# QS30-Main.net
KiCad netlist of a schematic drawn in Altium Designer
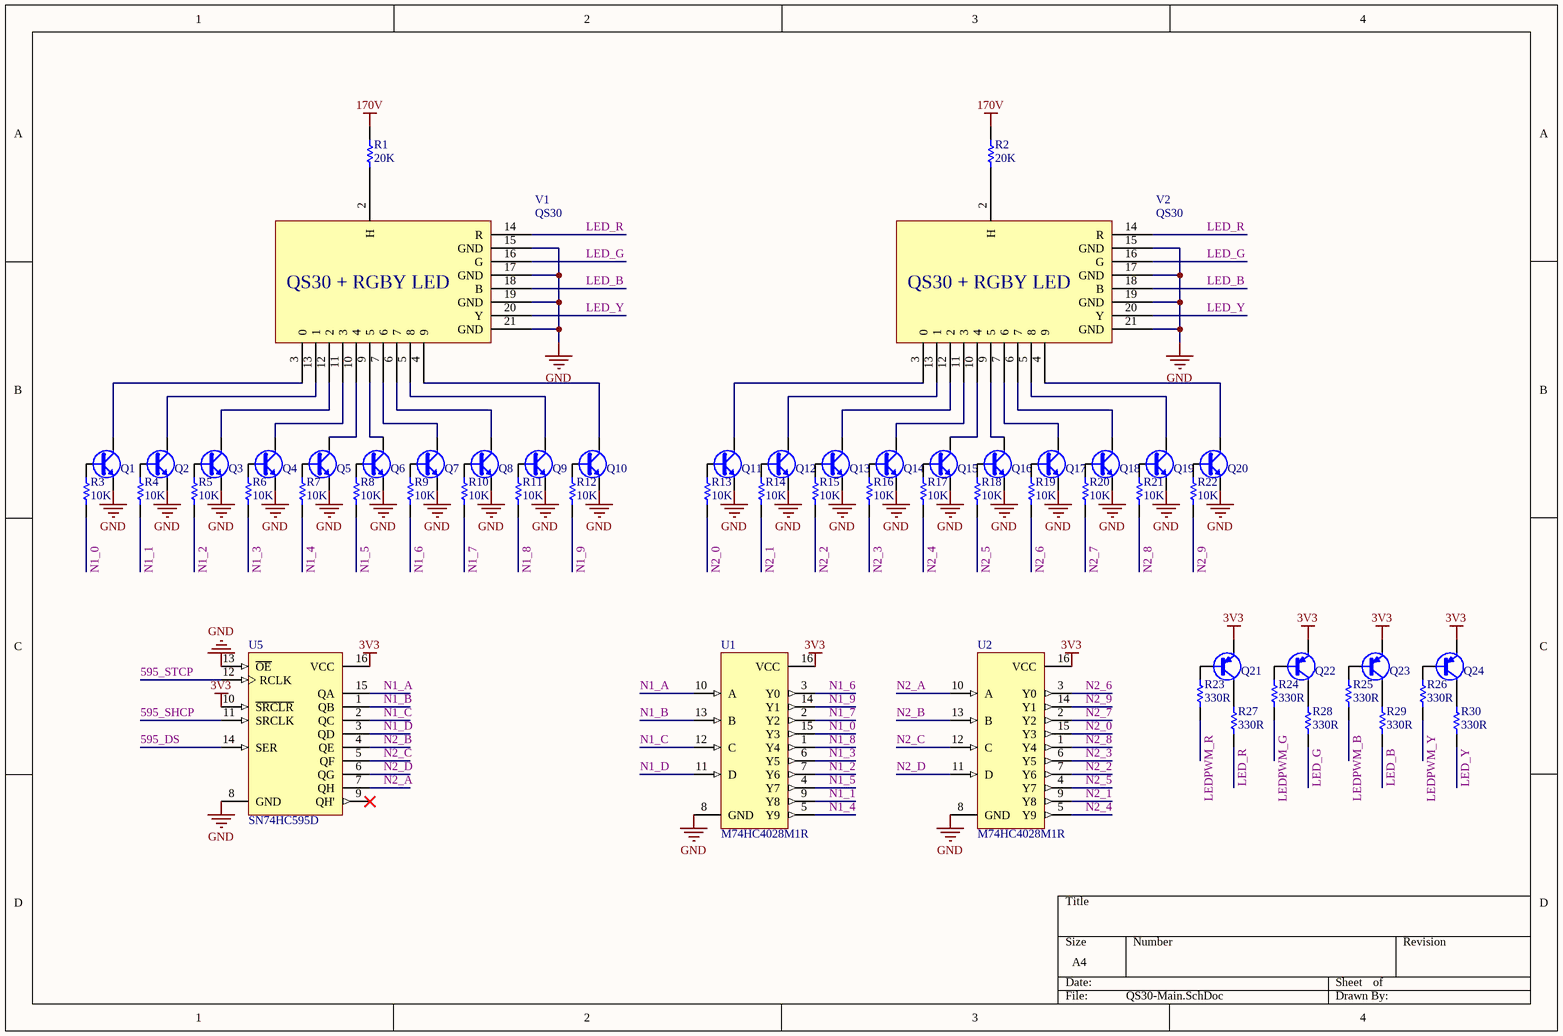
[diagram p0: QS30-Main.SchDoc]

(export (version "E")
  (design (tool "Eeschema 10.0.6"))
  (components
    (comp (ref "Q1") (value "MMBTA42") (footprint "SOT-23B_L") (libsource (lib "MINE") (part "MMBTA42")))
    (comp (ref "Q2") (value "MMBTA42") (footprint "SOT-23B_L") (libsource (lib "MINE") (part "MMBTA42")))
    (comp (ref "Q3") (value "MMBTA42") (footprint "SOT-23B_L") (libsource (lib "MINE") (part "MMBTA42")))
    (comp (ref "Q4") (value "MMBTA42") (footprint "SOT-23B_L") (libsource (lib "MINE") (part "MMBTA42")))
    (comp (ref "Q5") (value "MMBTA42") (footprint "SOT-23B_L") (libsource (lib "MINE") (part "MMBTA42")))
    (comp (ref "Q6") (value "MMBTA42") (footprint "SOT-23B_L") (libsource (lib "MINE") (part "MMBTA42")))
    (comp (ref "Q7") (value "MMBTA42") (footprint "SOT-23B_L") (libsource (lib "MINE") (part "MMBTA42")))
    (comp (ref "Q8") (value "MMBTA42") (footprint "SOT-23B_L") (libsource (lib "MINE") (part "MMBTA42")))
    (comp (ref "Q9") (value "MMBTA42") (footprint "SOT-23B_L") (libsource (lib "MINE") (part "MMBTA42")))
    (comp (ref "Q10") (value "MMBTA42") (footprint "SOT-23B_L") (libsource (lib "MINE") (part "MMBTA42")))
    (comp (ref "Q11") (value "MMBTA42") (footprint "SOT-23B_L") (libsource (lib "MINE") (part "MMBTA42")))
    (comp (ref "Q12") (value "MMBTA42") (footprint "SOT-23B_L") (libsource (lib "MINE") (part "MMBTA42")))
    (comp (ref "Q13") (value "MMBTA42") (footprint "SOT-23B_L") (libsource (lib "MINE") (part "MMBTA42")))
    (comp (ref "Q14") (value "MMBTA42") (footprint "SOT-23B_L") (libsource (lib "MINE") (part "MMBTA42")))
    (comp (ref "Q15") (value "MMBTA42") (footprint "SOT-23B_L") (libsource (lib "MINE") (part "MMBTA42")))
    (comp (ref "Q16") (value "MMBTA42") (footprint "SOT-23B_L") (libsource (lib "MINE") (part "MMBTA42")))
    (comp (ref "Q17") (value "MMBTA42") (footprint "SOT-23B_L") (libsource (lib "MINE") (part "MMBTA42")))
    (comp (ref "Q18") (value "MMBTA42") (footprint "SOT-23B_L") (libsource (lib "MINE") (part "MMBTA42")))
    (comp (ref "Q19") (value "MMBTA42") (footprint "SOT-23B_L") (libsource (lib "MINE") (part "MMBTA42")))
    (comp (ref "Q20") (value "MMBTA42") (footprint "SOT-23B_L") (libsource (lib "MINE") (part "MMBTA42")))
    (comp (ref "Q21")
      (value "9012 8550")
      (footprint "SOT-23")
      (description "PNP")
      (libsource (lib "常用封装库") (part "9012 8550"))
    )
    (comp (ref "Q22")
      (value "9012 8550")
      (footprint "SOT-23")
      (description "PNP")
      (libsource (lib "常用封装库") (part "9012 8550"))
    )
    (comp (ref "Q23")
      (value "9012 8550")
      (footprint "SOT-23")
      (description "PNP")
      (libsource (lib "常用封装库") (part "9012 8550"))
    )
    (comp (ref "Q24")
      (value "9012 8550")
      (footprint "SOT-23")
      (description "PNP")
      (libsource (lib "常用封装库") (part "9012 8550"))
    )
    (comp (ref "R1")
      (value "20K")
      (footprint "6-0805_N")
      (description "Resistor")
      (fields (field (name "Comment") "Res1") (field (name "PUBLISHER") "Altium Limited"))
      (libsource (lib "Miscellaneous Devices") (part "Res1"))
    )
    (comp (ref "R2")
      (value "20K")
      (footprint "6-0805_N")
      (description "Resistor")
      (fields (field (name "Comment") "Res1") (field (name "PUBLISHER") "Altium Limited"))
      (libsource (lib "Miscellaneous Devices") (part "Res1"))
    )
    (comp (ref "R3")
      (value "10K")
      (footprint "6-0805_N")
      (description "Resistor")
      (fields (field (name "Comment") "Res1") (field (name "PUBLISHER") "Altium Limited"))
      (libsource (lib "Miscellaneous Devices") (part "Res1"))
    )
    (comp (ref "R4")
      (value "10K")
      (footprint "6-0805_N")
      (description "Resistor")
      (fields (field (name "Comment") "Res1") (field (name "PUBLISHER") "Altium Limited"))
      (libsource (lib "Miscellaneous Devices") (part "Res1"))
    )
    (comp (ref "R5")
      (value "10K")
      (footprint "6-0805_N")
      (description "Resistor")
      (fields (field (name "Comment") "Res1") (field (name "PUBLISHER") "Altium Limited"))
      (libsource (lib "Miscellaneous Devices") (part "Res1"))
    )
    (comp (ref "R6")
      (value "10K")
      (footprint "6-0805_N")
      (description "Resistor")
      (fields (field (name "Comment") "Res1") (field (name "PUBLISHER") "Altium Limited"))
      (libsource (lib "Miscellaneous Devices") (part "Res1"))
    )
    (comp (ref "R7")
      (value "10K")
      (footprint "6-0805_N")
      (description "Resistor")
      (fields (field (name "Comment") "Res1") (field (name "PUBLISHER") "Altium Limited"))
      (libsource (lib "Miscellaneous Devices") (part "Res1"))
    )
    (comp (ref "R8")
      (value "10K")
      (footprint "6-0805_N")
      (description "Resistor")
      (fields (field (name "Comment") "Res1") (field (name "PUBLISHER") "Altium Limited"))
      (libsource (lib "Miscellaneous Devices") (part "Res1"))
    )
    (comp (ref "R9")
      (value "10K")
      (footprint "6-0805_N")
      (description "Resistor")
      (fields (field (name "Comment") "Res1") (field (name "PUBLISHER") "Altium Limited"))
      (libsource (lib "Miscellaneous Devices") (part "Res1"))
    )
    (comp (ref "R10")
      (value "10K")
      (footprint "6-0805_N")
      (description "Resistor")
      (fields (field (name "Comment") "Res1") (field (name "PUBLISHER") "Altium Limited"))
      (libsource (lib "Miscellaneous Devices") (part "Res1"))
    )
    (comp (ref "R11")
      (value "10K")
      (footprint "6-0805_N")
      (description "Resistor")
      (fields (field (name "Comment") "Res1") (field (name "PUBLISHER") "Altium Limited"))
      (libsource (lib "Miscellaneous Devices") (part "Res1"))
    )
    (comp (ref "R12")
      (value "10K")
      (footprint "6-0805_N")
      (description "Resistor")
      (fields (field (name "Comment") "Res1") (field (name "PUBLISHER") "Altium Limited"))
      (libsource (lib "Miscellaneous Devices") (part "Res1"))
    )
    (comp (ref "R13")
      (value "10K")
      (footprint "6-0805_N")
      (description "Resistor")
      (fields (field (name "Comment") "Res1") (field (name "PUBLISHER") "Altium Limited"))
      (libsource (lib "Miscellaneous Devices") (part "Res1"))
    )
    (comp (ref "R14")
      (value "10K")
      (footprint "6-0805_N")
      (description "Resistor")
      (fields (field (name "Comment") "Res1") (field (name "PUBLISHER") "Altium Limited"))
      (libsource (lib "Miscellaneous Devices") (part "Res1"))
    )
    (comp (ref "R15")
      (value "10K")
      (footprint "6-0805_N")
      (description "Resistor")
      (fields (field (name "Comment") "Res1") (field (name "PUBLISHER") "Altium Limited"))
      (libsource (lib "Miscellaneous Devices") (part "Res1"))
    )
    (comp (ref "R16")
      (value "10K")
      (footprint "6-0805_N")
      (description "Resistor")
      (fields (field (name "Comment") "Res1") (field (name "PUBLISHER") "Altium Limited"))
      (libsource (lib "Miscellaneous Devices") (part "Res1"))
    )
    (comp (ref "R17")
      (value "10K")
      (footprint "6-0805_N")
      (description "Resistor")
      (fields (field (name "Comment") "Res1") (field (name "PUBLISHER") "Altium Limited"))
      (libsource (lib "Miscellaneous Devices") (part "Res1"))
    )
    (comp (ref "R18")
      (value "10K")
      (footprint "6-0805_N")
      (description "Resistor")
      (fields (field (name "Comment") "Res1") (field (name "PUBLISHER") "Altium Limited"))
      (libsource (lib "Miscellaneous Devices") (part "Res1"))
    )
    (comp (ref "R19")
      (value "10K")
      (footprint "6-0805_N")
      (description "Resistor")
      (fields (field (name "Comment") "Res1") (field (name "PUBLISHER") "Altium Limited"))
      (libsource (lib "Miscellaneous Devices") (part "Res1"))
    )
    (comp (ref "R20")
      (value "10K")
      (footprint "6-0805_N")
      (description "Resistor")
      (fields (field (name "Comment") "Res1") (field (name "PUBLISHER") "Altium Limited"))
      (libsource (lib "Miscellaneous Devices") (part "Res1"))
    )
    (comp (ref "R21")
      (value "10K")
      (footprint "6-0805_N")
      (description "Resistor")
      (fields (field (name "Comment") "Res1") (field (name "PUBLISHER") "Altium Limited"))
      (libsource (lib "Miscellaneous Devices") (part "Res1"))
    )
    (comp (ref "R22")
      (value "10K")
      (footprint "6-0805_N")
      (description "Resistor")
      (fields (field (name "Comment") "Res1") (field (name "PUBLISHER") "Altium Limited"))
      (libsource (lib "Miscellaneous Devices") (part "Res1"))
    )
    (comp (ref "R23")
      (value "330R")
      (footprint "6-0805_N")
      (description "Resistor")
      (fields (field (name "Comment") "Res1") (field (name "PUBLISHER") "Altium Limited"))
      (libsource (lib "Miscellaneous Devices") (part "Res1"))
    )
    (comp (ref "R24")
      (value "330R")
      (footprint "6-0805_N")
      (description "Resistor")
      (fields (field (name "Comment") "Res1") (field (name "PUBLISHER") "Altium Limited"))
      (libsource (lib "Miscellaneous Devices") (part "Res1"))
    )
    (comp (ref "R25")
      (value "330R")
      (footprint "6-0805_N")
      (description "Resistor")
      (fields (field (name "Comment") "Res1") (field (name "PUBLISHER") "Altium Limited"))
      (libsource (lib "Miscellaneous Devices") (part "Res1"))
    )
    (comp (ref "R26")
      (value "330R")
      (footprint "6-0805_N")
      (description "Resistor")
      (fields (field (name "Comment") "Res1") (field (name "PUBLISHER") "Altium Limited"))
      (libsource (lib "Miscellaneous Devices") (part "Res1"))
    )
    (comp (ref "R27")
      (value "330R")
      (footprint "6-0805_N")
      (description "Resistor")
      (fields (field (name "Comment") "Res1") (field (name "PUBLISHER") "Altium Limited"))
      (libsource (lib "Miscellaneous Devices") (part "Res1"))
    )
    (comp (ref "R28")
      (value "330R")
      (footprint "6-0805_N")
      (description "Resistor")
      (fields (field (name "Comment") "Res1") (field (name "PUBLISHER") "Altium Limited"))
      (libsource (lib "Miscellaneous Devices") (part "Res1"))
    )
    (comp (ref "R29")
      (value "330R")
      (footprint "6-0805_N")
      (description "Resistor")
      (fields (field (name "Comment") "Res1") (field (name "PUBLISHER") "Altium Limited"))
      (libsource (lib "Miscellaneous Devices") (part "Res1"))
    )
    (comp (ref "R30")
      (value "330R")
      (footprint "6-0805_N")
      (description "Resistor")
      (fields (field (name "Comment") "Res1") (field (name "PUBLISHER") "Altium Limited"))
      (libsource (lib "Miscellaneous Devices") (part "Res1"))
    )
    (comp (ref "U1")
      (value "M74HC4028M1R")
      (footprint "SO16_N")
      (description "BCD-to-Decimal Decoder")
      (fields (field (name "PUBLISHER") "Altium Limited"))
      (libsource (lib "ST Logic Decoder") (part "M74HC4028M1R"))
    )
    (comp (ref "U2")
      (value "M74HC4028M1R")
      (footprint "SO16_N")
      (description "BCD-to-Decimal Decoder")
      (fields (field (name "PUBLISHER") "Altium Limited"))
      (libsource (lib "ST Logic Decoder") (part "M74HC4028M1R"))
    )
    (comp (ref "U5")
      (value "SN74HC595D")
      (footprint "D016_N")
      (description "8-Bit Shift Register with 3-State Output Registers")
      (fields (field (name "PUBLISHER") "Altium Limited"))
      (libsource (lib "TI Logic Register") (part "SN74HC595D"))
    )
    (comp (ref "V1") (value "QS30") (footprint "QS30") (libsource (lib "常用封装库") (part "QS30")))
    (comp (ref "V2") (value "QS30") (footprint "QS30") (libsource (lib "常用封装库") (part "QS30")))
  )
  (nets
    (net (code "1") (name "/595_DS") (class "Default")
      (node (ref "U5") (pin "14") (pinfunction "SER_14") (pintype "input"))
    )
    (net (code "2") (name "/595_SHCP") (class "Default")
      (node (ref "U5") (pin "11") (pinfunction "SRCLK_11") (pintype "input"))
    )
    (net (code "3") (name "/595_STCP") (class "Default")
      (node (ref "U5") (pin "12") (pinfunction "RCLK_12") (pintype "input"))
    )
    (net (code "4") (name "/LEDPWM_B") (class "Default")
      (node (ref "R25") (pin "1") (pinfunction "1_1") (pintype "passive"))
    )
    (net (code "5") (name "/LEDPWM_G") (class "Default")
      (node (ref "R24") (pin "1") (pinfunction "1_1") (pintype "passive"))
    )
    (net (code "6") (name "/LEDPWM_R") (class "Default")
      (node (ref "R23") (pin "1") (pinfunction "1_1") (pintype "passive"))
    )
    (net (code "7") (name "/LEDPWM_Y") (class "Default")
      (node (ref "R26") (pin "1") (pinfunction "1_1") (pintype "passive"))
    )
    (net (code "8") (name "/LED_B") (class "Default")
      (node (ref "R29") (pin "1") (pinfunction "1_1") (pintype "passive"))
      (node (ref "V1") (pin "18") (pinfunction "B_18") (pintype "passive"))
      (node (ref "V2") (pin "18") (pinfunction "B_18") (pintype "passive"))
    )
    (net (code "9") (name "/LED_G") (class "Default")
      (node (ref "R28") (pin "1") (pinfunction "1_1") (pintype "passive"))
      (node (ref "V1") (pin "16") (pinfunction "G_16") (pintype "passive"))
      (node (ref "V2") (pin "16") (pinfunction "G_16") (pintype "passive"))
    )
    (net (code "10") (name "/LED_R") (class "Default")
      (node (ref "R27") (pin "1") (pinfunction "1_1") (pintype "passive"))
      (node (ref "V1") (pin "14") (pinfunction "R_14") (pintype "passive"))
      (node (ref "V2") (pin "14") (pinfunction "R_14") (pintype "passive"))
    )
    (net (code "11") (name "/LED_Y") (class "Default")
      (node (ref "R30") (pin "1") (pinfunction "1_1") (pintype "passive"))
      (node (ref "V1") (pin "20") (pinfunction "Y_20") (pintype "passive"))
      (node (ref "V2") (pin "20") (pinfunction "Y_20") (pintype "passive"))
    )
    (net (code "12") (name "/N1_0") (class "Default")
      (node (ref "R3") (pin "2") (pinfunction "2_2") (pintype "passive"))
      (node (ref "U1") (pin "15") (pinfunction "Y3_15") (pintype "output"))
    )
    (net (code "13") (name "/N1_1") (class "Default")
      (node (ref "R4") (pin "2") (pinfunction "2_2") (pintype "passive"))
      (node (ref "U1") (pin "9") (pinfunction "Y8_9") (pintype "output"))
    )
    (net (code "14") (name "/N1_2") (class "Default")
      (node (ref "R5") (pin "2") (pinfunction "2_2") (pintype "passive"))
      (node (ref "U1") (pin "7") (pinfunction "Y6_7") (pintype "output"))
    )
    (net (code "15") (name "/N1_3") (class "Default")
      (node (ref "R6") (pin "2") (pinfunction "2_2") (pintype "passive"))
      (node (ref "U1") (pin "6") (pinfunction "Y5_6") (pintype "output"))
    )
    (net (code "16") (name "/N1_4") (class "Default")
      (node (ref "R7") (pin "2") (pinfunction "2_2") (pintype "passive"))
      (node (ref "U1") (pin "5") (pinfunction "Y9_5") (pintype "output"))
    )
    (net (code "17") (name "/N1_5") (class "Default")
      (node (ref "R8") (pin "2") (pinfunction "2_2") (pintype "passive"))
      (node (ref "U1") (pin "4") (pinfunction "Y7_4") (pintype "output"))
    )
    (net (code "18") (name "/N1_6") (class "Default")
      (node (ref "R9") (pin "2") (pinfunction "2_2") (pintype "passive"))
      (node (ref "U1") (pin "3") (pinfunction "Y0_3") (pintype "output"))
    )
    (net (code "19") (name "/N1_7") (class "Default")
      (node (ref "R10") (pin "2") (pinfunction "2_2") (pintype "passive"))
      (node (ref "U1") (pin "2") (pinfunction "Y2_2") (pintype "output"))
    )
    (net (code "20") (name "/N1_8") (class "Default")
      (node (ref "R11") (pin "2") (pinfunction "2_2") (pintype "passive"))
      (node (ref "U1") (pin "1") (pinfunction "Y4_1") (pintype "output"))
    )
    (net (code "21") (name "/N1_9") (class "Default")
      (node (ref "R12") (pin "2") (pinfunction "2_2") (pintype "passive"))
      (node (ref "U1") (pin "14") (pinfunction "Y1_14") (pintype "output"))
    )
    (net (code "22") (name "/N1_A") (class "Default")
      (node (ref "U1") (pin "10") (pinfunction "A_10") (pintype "input"))
      (node (ref "U5") (pin "15") (pinfunction "QA_15") (pintype "tri_state"))
    )
    (net (code "23") (name "/N1_B") (class "Default")
      (node (ref "U1") (pin "13") (pinfunction "B_13") (pintype "input"))
      (node (ref "U5") (pin "1") (pinfunction "QB_1") (pintype "tri_state"))
    )
    (net (code "24") (name "/N1_C") (class "Default")
      (node (ref "U1") (pin "12") (pinfunction "C_12") (pintype "input"))
      (node (ref "U5") (pin "2") (pinfunction "QC_2") (pintype "tri_state"))
    )
    (net (code "25") (name "/N1_D") (class "Default")
      (node (ref "U1") (pin "11") (pinfunction "D_11") (pintype "input"))
      (node (ref "U5") (pin "3") (pinfunction "QD_3") (pintype "tri_state"))
    )
    (net (code "26") (name "/N2_0") (class "Default")
      (node (ref "R13") (pin "2") (pinfunction "2_2") (pintype "passive"))
      (node (ref "U2") (pin "15") (pinfunction "Y3_15") (pintype "output"))
    )
    (net (code "27") (name "/N2_1") (class "Default")
      (node (ref "R14") (pin "2") (pinfunction "2_2") (pintype "passive"))
      (node (ref "U2") (pin "9") (pinfunction "Y8_9") (pintype "output"))
    )
    (net (code "28") (name "/N2_2") (class "Default")
      (node (ref "R15") (pin "2") (pinfunction "2_2") (pintype "passive"))
      (node (ref "U2") (pin "7") (pinfunction "Y6_7") (pintype "output"))
    )
    (net (code "29") (name "/N2_3") (class "Default")
      (node (ref "R16") (pin "2") (pinfunction "2_2") (pintype "passive"))
      (node (ref "U2") (pin "6") (pinfunction "Y5_6") (pintype "output"))
    )
    (net (code "30") (name "/N2_4") (class "Default")
      (node (ref "R17") (pin "2") (pinfunction "2_2") (pintype "passive"))
      (node (ref "U2") (pin "5") (pinfunction "Y9_5") (pintype "output"))
    )
    (net (code "31") (name "/N2_5") (class "Default")
      (node (ref "R18") (pin "2") (pinfunction "2_2") (pintype "passive"))
      (node (ref "U2") (pin "4") (pinfunction "Y7_4") (pintype "output"))
    )
    (net (code "32") (name "/N2_6") (class "Default")
      (node (ref "R19") (pin "2") (pinfunction "2_2") (pintype "passive"))
      (node (ref "U2") (pin "3") (pinfunction "Y0_3") (pintype "output"))
    )
    (net (code "33") (name "/N2_7") (class "Default")
      (node (ref "R20") (pin "2") (pinfunction "2_2") (pintype "passive"))
      (node (ref "U2") (pin "2") (pinfunction "Y2_2") (pintype "output"))
    )
    (net (code "34") (name "/N2_8") (class "Default")
      (node (ref "R21") (pin "2") (pinfunction "2_2") (pintype "passive"))
      (node (ref "U2") (pin "1") (pinfunction "Y4_1") (pintype "output"))
    )
    (net (code "35") (name "/N2_9") (class "Default")
      (node (ref "R22") (pin "2") (pinfunction "2_2") (pintype "passive"))
      (node (ref "U2") (pin "14") (pinfunction "Y1_14") (pintype "output"))
    )
    (net (code "36") (name "/N2_A") (class "Default")
      (node (ref "U2") (pin "10") (pinfunction "A_10") (pintype "input"))
      (node (ref "U5") (pin "7") (pinfunction "QH_7") (pintype "tri_state"))
    )
    (net (code "37") (name "/N2_B") (class "Default")
      (node (ref "U2") (pin "13") (pinfunction "B_13") (pintype "input"))
      (node (ref "U5") (pin "4") (pinfunction "QE_4") (pintype "tri_state"))
    )
    (net (code "38") (name "/N2_C") (class "Default")
      (node (ref "U2") (pin "12") (pinfunction "C_12") (pintype "input"))
      (node (ref "U5") (pin "5") (pinfunction "QF_5") (pintype "tri_state"))
    )
    (net (code "39") (name "/N2_D") (class "Default")
      (node (ref "U2") (pin "11") (pinfunction "D_11") (pintype "input"))
      (node (ref "U5") (pin "6") (pinfunction "QG_6") (pintype "tri_state"))
    )
    (net (code "40") (name "3V3") (class "Default")
      (node (ref "Q21") (pin "2") (pinfunction "e_2") (pintype "passive"))
      (node (ref "Q22") (pin "2") (pinfunction "e_2") (pintype "passive"))
      (node (ref "Q23") (pin "2") (pinfunction "e_2") (pintype "passive"))
      (node (ref "Q24") (pin "2") (pinfunction "e_2") (pintype "passive"))
      (node (ref "U1") (pin "16") (pinfunction "VCC_16") (pintype "power_in"))
      (node (ref "U2") (pin "16") (pinfunction "VCC_16") (pintype "power_in"))
      (node (ref "U5") (pin "10") (pinfunction "~{SRCLR}_10") (pintype "input"))
      (node (ref "U5") (pin "16") (pinfunction "VCC_16") (pintype "power_in"))
    )
    (net (code "41") (name "170V") (class "Default")
      (node (ref "R1") (pin "1") (pinfunction "1_1") (pintype "passive"))
      (node (ref "R2") (pin "1") (pinfunction "1_1") (pintype "passive"))
    )
    (net (code "42") (name "GND") (class "Default")
      (node (ref "Q1") (pin "2") (pinfunction "E_2") (pintype "passive"))
      (node (ref "Q10") (pin "2") (pinfunction "E_2") (pintype "passive"))
      (node (ref "Q11") (pin "2") (pinfunction "E_2") (pintype "passive"))
      (node (ref "Q12") (pin "2") (pinfunction "E_2") (pintype "passive"))
      (node (ref "Q13") (pin "2") (pinfunction "E_2") (pintype "passive"))
      (node (ref "Q14") (pin "2") (pinfunction "E_2") (pintype "passive"))
      (node (ref "Q15") (pin "2") (pinfunction "E_2") (pintype "passive"))
      (node (ref "Q16") (pin "2") (pinfunction "E_2") (pintype "passive"))
      (node (ref "Q17") (pin "2") (pinfunction "E_2") (pintype "passive"))
      (node (ref "Q18") (pin "2") (pinfunction "E_2") (pintype "passive"))
      (node (ref "Q19") (pin "2") (pinfunction "E_2") (pintype "passive"))
      (node (ref "Q2") (pin "2") (pinfunction "E_2") (pintype "passive"))
      (node (ref "Q20") (pin "2") (pinfunction "E_2") (pintype "passive"))
      (node (ref "Q3") (pin "2") (pinfunction "E_2") (pintype "passive"))
      (node (ref "Q4") (pin "2") (pinfunction "E_2") (pintype "passive"))
      (node (ref "Q5") (pin "2") (pinfunction "E_2") (pintype "passive"))
      (node (ref "Q6") (pin "2") (pinfunction "E_2") (pintype "passive"))
      (node (ref "Q7") (pin "2") (pinfunction "E_2") (pintype "passive"))
      (node (ref "Q8") (pin "2") (pinfunction "E_2") (pintype "passive"))
      (node (ref "Q9") (pin "2") (pinfunction "E_2") (pintype "passive"))
      (node (ref "U1") (pin "8") (pinfunction "GND_8") (pintype "power_in"))
      (node (ref "U2") (pin "8") (pinfunction "GND_8") (pintype "power_in"))
      (node (ref "U5") (pin "13") (pinfunction "~{OE}_13") (pintype "input"))
      (node (ref "U5") (pin "8") (pinfunction "GND_8") (pintype "power_in"))
      (node (ref "V1") (pin "15") (pinfunction "GND_15") (pintype "passive"))
      (node (ref "V1") (pin "17") (pinfunction "GND_17") (pintype "passive"))
      (node (ref "V1") (pin "19") (pinfunction "GND_19") (pintype "passive"))
      (node (ref "V1") (pin "21") (pinfunction "GND_21") (pintype "passive"))
      (node (ref "V2") (pin "15") (pinfunction "GND_15") (pintype "passive"))
      (node (ref "V2") (pin "17") (pinfunction "GND_17") (pintype "passive"))
      (node (ref "V2") (pin "19") (pinfunction "GND_19") (pintype "passive"))
      (node (ref "V2") (pin "21") (pinfunction "GND_21") (pintype "passive"))
    )
    (net (code "43") (name "Net-(Q1-B)") (class "Default")
      (node (ref "Q1") (pin "1") (pinfunction "B_1") (pintype "passive"))
      (node (ref "R3") (pin "1") (pinfunction "1_1") (pintype "passive"))
    )
    (net (code "44") (name "Net-(Q1-C)") (class "Default")
      (node (ref "Q1") (pin "3") (pinfunction "C_3") (pintype "passive"))
      (node (ref "V1") (pin "3") (pinfunction "0_3") (pintype "passive"))
    )
    (net (code "45") (name "Net-(Q2-B)") (class "Default")
      (node (ref "Q2") (pin "1") (pinfunction "B_1") (pintype "passive"))
      (node (ref "R4") (pin "1") (pinfunction "1_1") (pintype "passive"))
    )
    (net (code "46") (name "Net-(Q2-C)") (class "Default")
      (node (ref "Q2") (pin "3") (pinfunction "C_3") (pintype "passive"))
      (node (ref "V1") (pin "13") (pinfunction "1_13") (pintype "passive"))
    )
    (net (code "47") (name "Net-(Q3-B)") (class "Default")
      (node (ref "Q3") (pin "1") (pinfunction "B_1") (pintype "passive"))
      (node (ref "R5") (pin "1") (pinfunction "1_1") (pintype "passive"))
    )
    (net (code "48") (name "Net-(Q3-C)") (class "Default")
      (node (ref "Q3") (pin "3") (pinfunction "C_3") (pintype "passive"))
      (node (ref "V1") (pin "12") (pinfunction "2_12") (pintype "passive"))
    )
    (net (code "49") (name "Net-(Q4-B)") (class "Default")
      (node (ref "Q4") (pin "1") (pinfunction "B_1") (pintype "passive"))
      (node (ref "R6") (pin "1") (pinfunction "1_1") (pintype "passive"))
    )
    (net (code "50") (name "Net-(Q4-C)") (class "Default")
      (node (ref "Q4") (pin "3") (pinfunction "C_3") (pintype "passive"))
      (node (ref "V1") (pin "11") (pinfunction "3_11") (pintype "passive"))
    )
    (net (code "51") (name "Net-(Q5-B)") (class "Default")
      (node (ref "Q5") (pin "1") (pinfunction "B_1") (pintype "passive"))
      (node (ref "R7") (pin "1") (pinfunction "1_1") (pintype "passive"))
    )
    (net (code "52") (name "Net-(Q5-C)") (class "Default")
      (node (ref "Q5") (pin "3") (pinfunction "C_3") (pintype "passive"))
      (node (ref "V1") (pin "10") (pinfunction "4_10") (pintype "passive"))
    )
    (net (code "53") (name "Net-(Q6-B)") (class "Default")
      (node (ref "Q6") (pin "1") (pinfunction "B_1") (pintype "passive"))
      (node (ref "R8") (pin "1") (pinfunction "1_1") (pintype "passive"))
    )
    (net (code "54") (name "Net-(Q6-C)") (class "Default")
      (node (ref "Q6") (pin "3") (pinfunction "C_3") (pintype "passive"))
      (node (ref "V1") (pin "9") (pinfunction "5_9") (pintype "passive"))
    )
    (net (code "55") (name "Net-(Q7-B)") (class "Default")
      (node (ref "Q7") (pin "1") (pinfunction "B_1") (pintype "passive"))
      (node (ref "R9") (pin "1") (pinfunction "1_1") (pintype "passive"))
    )
    (net (code "56") (name "Net-(Q7-C)") (class "Default")
      (node (ref "Q7") (pin "3") (pinfunction "C_3") (pintype "passive"))
      (node (ref "V1") (pin "7") (pinfunction "6_7") (pintype "passive"))
    )
    (net (code "57") (name "Net-(Q8-B)") (class "Default")
      (node (ref "Q8") (pin "1") (pinfunction "B_1") (pintype "passive"))
      (node (ref "R10") (pin "1") (pinfunction "1_1") (pintype "passive"))
    )
    (net (code "58") (name "Net-(Q8-C)") (class "Default")
      (node (ref "Q8") (pin "3") (pinfunction "C_3") (pintype "passive"))
      (node (ref "V1") (pin "6") (pinfunction "7_6") (pintype "passive"))
    )
    (net (code "59") (name "Net-(Q9-B)") (class "Default")
      (node (ref "Q9") (pin "1") (pinfunction "B_1") (pintype "passive"))
      (node (ref "R11") (pin "1") (pinfunction "1_1") (pintype "passive"))
    )
    (net (code "60") (name "Net-(Q9-C)") (class "Default")
      (node (ref "Q9") (pin "3") (pinfunction "C_3") (pintype "passive"))
      (node (ref "V1") (pin "5") (pinfunction "8_5") (pintype "passive"))
    )
    (net (code "61") (name "Net-(Q10-B)") (class "Default")
      (node (ref "Q10") (pin "1") (pinfunction "B_1") (pintype "passive"))
      (node (ref "R12") (pin "1") (pinfunction "1_1") (pintype "passive"))
    )
    (net (code "62") (name "Net-(Q10-C)") (class "Default")
      (node (ref "Q10") (pin "3") (pinfunction "C_3") (pintype "passive"))
      (node (ref "V1") (pin "4") (pinfunction "9_4") (pintype "passive"))
    )
    (net (code "63") (name "Net-(Q11-B)") (class "Default")
      (node (ref "Q11") (pin "1") (pinfunction "B_1") (pintype "passive"))
      (node (ref "R13") (pin "1") (pinfunction "1_1") (pintype "passive"))
    )
    (net (code "64") (name "Net-(Q11-C)") (class "Default")
      (node (ref "Q11") (pin "3") (pinfunction "C_3") (pintype "passive"))
      (node (ref "V2") (pin "3") (pinfunction "0_3") (pintype "passive"))
    )
    (net (code "65") (name "Net-(Q12-B)") (class "Default")
      (node (ref "Q12") (pin "1") (pinfunction "B_1") (pintype "passive"))
      (node (ref "R14") (pin "1") (pinfunction "1_1") (pintype "passive"))
    )
    (net (code "66") (name "Net-(Q12-C)") (class "Default")
      (node (ref "Q12") (pin "3") (pinfunction "C_3") (pintype "passive"))
      (node (ref "V2") (pin "13") (pinfunction "1_13") (pintype "passive"))
    )
    (net (code "67") (name "Net-(Q13-B)") (class "Default")
      (node (ref "Q13") (pin "1") (pinfunction "B_1") (pintype "passive"))
      (node (ref "R15") (pin "1") (pinfunction "1_1") (pintype "passive"))
    )
    (net (code "68") (name "Net-(Q13-C)") (class "Default")
      (node (ref "Q13") (pin "3") (pinfunction "C_3") (pintype "passive"))
      (node (ref "V2") (pin "12") (pinfunction "2_12") (pintype "passive"))
    )
    (net (code "69") (name "Net-(Q14-B)") (class "Default")
      (node (ref "Q14") (pin "1") (pinfunction "B_1") (pintype "passive"))
      (node (ref "R16") (pin "1") (pinfunction "1_1") (pintype "passive"))
    )
    (net (code "70") (name "Net-(Q14-C)") (class "Default")
      (node (ref "Q14") (pin "3") (pinfunction "C_3") (pintype "passive"))
      (node (ref "V2") (pin "11") (pinfunction "3_11") (pintype "passive"))
    )
    (net (code "71") (name "Net-(Q15-B)") (class "Default")
      (node (ref "Q15") (pin "1") (pinfunction "B_1") (pintype "passive"))
      (node (ref "R17") (pin "1") (pinfunction "1_1") (pintype "passive"))
    )
    (net (code "72") (name "Net-(Q15-C)") (class "Default")
      (node (ref "Q15") (pin "3") (pinfunction "C_3") (pintype "passive"))
      (node (ref "V2") (pin "10") (pinfunction "4_10") (pintype "passive"))
    )
    (net (code "73") (name "Net-(Q16-B)") (class "Default")
      (node (ref "Q16") (pin "1") (pinfunction "B_1") (pintype "passive"))
      (node (ref "R18") (pin "1") (pinfunction "1_1") (pintype "passive"))
    )
    (net (code "74") (name "Net-(Q16-C)") (class "Default")
      (node (ref "Q16") (pin "3") (pinfunction "C_3") (pintype "passive"))
      (node (ref "V2") (pin "9") (pinfunction "5_9") (pintype "passive"))
    )
    (net (code "75") (name "Net-(Q17-B)") (class "Default")
      (node (ref "Q17") (pin "1") (pinfunction "B_1") (pintype "passive"))
      (node (ref "R19") (pin "1") (pinfunction "1_1") (pintype "passive"))
    )
    (net (code "76") (name "Net-(Q17-C)") (class "Default")
      (node (ref "Q17") (pin "3") (pinfunction "C_3") (pintype "passive"))
      (node (ref "V2") (pin "7") (pinfunction "6_7") (pintype "passive"))
    )
    (net (code "77") (name "Net-(Q18-B)") (class "Default")
      (node (ref "Q18") (pin "1") (pinfunction "B_1") (pintype "passive"))
      (node (ref "R20") (pin "1") (pinfunction "1_1") (pintype "passive"))
    )
    (net (code "78") (name "Net-(Q18-C)") (class "Default")
      (node (ref "Q18") (pin "3") (pinfunction "C_3") (pintype "passive"))
      (node (ref "V2") (pin "6") (pinfunction "7_6") (pintype "passive"))
    )
    (net (code "79") (name "Net-(Q19-B)") (class "Default")
      (node (ref "Q19") (pin "1") (pinfunction "B_1") (pintype "passive"))
      (node (ref "R21") (pin "1") (pinfunction "1_1") (pintype "passive"))
    )
    (net (code "80") (name "Net-(Q19-C)") (class "Default")
      (node (ref "Q19") (pin "3") (pinfunction "C_3") (pintype "passive"))
      (node (ref "V2") (pin "5") (pinfunction "8_5") (pintype "passive"))
    )
    (net (code "81") (name "Net-(Q20-B)") (class "Default")
      (node (ref "Q20") (pin "1") (pinfunction "B_1") (pintype "passive"))
      (node (ref "R22") (pin "1") (pinfunction "1_1") (pintype "passive"))
    )
    (net (code "82") (name "Net-(Q20-C)") (class "Default")
      (node (ref "Q20") (pin "3") (pinfunction "C_3") (pintype "passive"))
      (node (ref "V2") (pin "4") (pinfunction "9_4") (pintype "passive"))
    )
    (net (code "83") (name "Net-(Q21-b)") (class "Default")
      (node (ref "Q21") (pin "1") (pinfunction "b_1") (pintype "passive"))
      (node (ref "R23") (pin "2") (pinfunction "2_2") (pintype "passive"))
    )
    (net (code "84") (name "Net-(Q21-c)") (class "Default")
      (node (ref "Q21") (pin "3") (pinfunction "c_3") (pintype "passive"))
      (node (ref "R27") (pin "2") (pinfunction "2_2") (pintype "passive"))
    )
    (net (code "85") (name "Net-(Q22-b)") (class "Default")
      (node (ref "Q22") (pin "1") (pinfunction "b_1") (pintype "passive"))
      (node (ref "R24") (pin "2") (pinfunction "2_2") (pintype "passive"))
    )
    (net (code "86") (name "Net-(Q22-c)") (class "Default")
      (node (ref "Q22") (pin "3") (pinfunction "c_3") (pintype "passive"))
      (node (ref "R28") (pin "2") (pinfunction "2_2") (pintype "passive"))
    )
    (net (code "87") (name "Net-(Q23-b)") (class "Default")
      (node (ref "Q23") (pin "1") (pinfunction "b_1") (pintype "passive"))
      (node (ref "R25") (pin "2") (pinfunction "2_2") (pintype "passive"))
    )
    (net (code "88") (name "Net-(Q23-c)") (class "Default")
      (node (ref "Q23") (pin "3") (pinfunction "c_3") (pintype "passive"))
      (node (ref "R29") (pin "2") (pinfunction "2_2") (pintype "passive"))
    )
    (net (code "89") (name "Net-(Q24-b)") (class "Default")
      (node (ref "Q24") (pin "1") (pinfunction "b_1") (pintype "passive"))
      (node (ref "R26") (pin "2") (pinfunction "2_2") (pintype "passive"))
    )
    (net (code "90") (name "Net-(Q24-c)") (class "Default")
      (node (ref "Q24") (pin "3") (pinfunction "c_3") (pintype "passive"))
      (node (ref "R30") (pin "2") (pinfunction "2_2") (pintype "passive"))
    )
    (net (code "91") (name "Net-(V1-H)") (class "Default")
      (node (ref "R1") (pin "2") (pinfunction "2_2") (pintype "passive"))
      (node (ref "V1") (pin "2") (pinfunction "H_2") (pintype "passive"))
    )
    (net (code "92") (name "Net-(V2-H)") (class "Default")
      (node (ref "R2") (pin "2") (pinfunction "2_2") (pintype "passive"))
      (node (ref "V2") (pin "2") (pinfunction "H_2") (pintype "passive"))
    )
    (net (code "93") (name "unconnected-(U5-QH'-Pad9)") (class "Default")
      (node (ref "U5") (pin "9") (pinfunction "QH'_9") (pintype "output+no_connect"))
    )
  )
)
